# Brake.net
KiCad netlist of a schematic drawn in Altium Designer
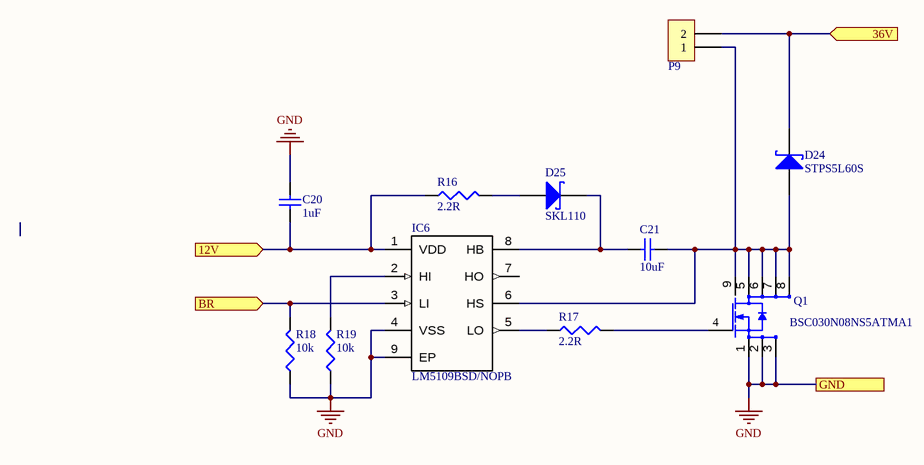
[diagram p0: Brake.SchDoc]

(export (version "E")
  (design (tool "Eeschema 10.0.6"))
  (components
    (comp (ref "C20")
      (value "1uF")
      (footprint "C1608-0603")
      (description "Керамическийконденсатор")
      (libsource (lib "db") (part "Cap"))
    )
    (comp (ref "C21")
      (value "10uF")
      (footprint "C1608-0603")
      (description "Керамическийконденсатор")
      (libsource (lib "db") (part "Cap"))
    )
    (comp (ref "D24")
      (value "STPS5L60S")
      (footprint "SMCJ")
      (description "Диод Шоттки 60В 5А [SMC]")
      (libsource (lib "db") (part "STPS5L60S"))
    )
    (comp (ref "D25")
      (value "SKL110")
      (footprint "SODFL370X140-2N")
      (description "Диод Шоттки 100В 1А")
      (libsource (lib "db") (part "SKL110"))
    )
    (comp (ref "IC6")
      (value "LM5109BSD/NOPB")
      (footprint "PSON80P400X80_HS-9N")
      (description "Драйвер MOSFET")
      (libsource (lib "db") (part "LM5109BSD/NOPB"))
    )
    (comp (ref "P9")
      (value "15EDGRC-3.81-02")
      (footprint "15EDGRC-3.81-02")
      (description "Разъем штыревой на плату (папа)")
      (libsource (lib "db") (part "15EDGRC-3.81-02"))
    )
    (comp (ref "Q1")
      (value "BSC030N08NS5ATMA1")
      (footprint "PG-TDSON-8")
      (description "N - канальный MOSFET")
      (libsource (lib "db") (part "BSC030N08NS5ATMA1"))
    )
    (comp (ref "R16")
      (value "2.2R")
      (footprint "R1608-0603")
      (description "SMD резистор")
      (libsource (lib "db") (part "resistor"))
    )
    (comp (ref "R17")
      (value "2.2R")
      (footprint "R1608-0603")
      (description "SMD резистор")
      (libsource (lib "db") (part "resistor"))
    )
    (comp (ref "R18")
      (value "10k")
      (footprint "R1608-0603")
      (description "SMD резистор")
      (libsource (lib "db") (part "resistor"))
    )
    (comp (ref "R19")
      (value "10k")
      (footprint "R1608-0603")
      (description "SMD резистор")
      (libsource (lib "db") (part "resistor"))
    )
  )
  (nets
    (net (code "1") (name "/12V") (class "Default")
      (node (ref "C20") (pin "1") (pinfunction "1_1") (pintype "passive"))
      (node (ref "IC6") (pin "1") (pinfunction "VDD_1") (pintype "power_in"))
      (node (ref "R16") (pin "1") (pinfunction "1_1") (pintype "passive"))
    )
    (net (code "2") (name "/36V") (class "Default")
      (node (ref "D24") (pin "1") (pinfunction "K_1") (pintype "passive"))
      (node (ref "P9") (pin "2") (pinfunction "2_2") (pintype "passive"))
    )
    (net (code "3") (name "/BR") (class "Default")
      (node (ref "IC6") (pin "3") (pinfunction "LI_3") (pintype "input"))
      (node (ref "R18") (pin "2") (pinfunction "2_2") (pintype "passive"))
    )
    (net (code "4") (name "GND") (class "Default")
      (node (ref "C20") (pin "2") (pinfunction "2_2") (pintype "passive"))
      (node (ref "IC6") (pin "4") (pinfunction "VSS_4") (pintype "power_in"))
      (node (ref "IC6") (pin "9") (pinfunction "EP_9") (pintype "passive"))
      (node (ref "Q1") (pin "1") (pinfunction "S_1") (pintype "passive"))
      (node (ref "Q1") (pin "2") (pinfunction "S_2") (pintype "passive"))
      (node (ref "Q1") (pin "3") (pinfunction "S_3") (pintype "passive"))
      (node (ref "R18") (pin "1") (pinfunction "1_1") (pintype "passive"))
      (node (ref "R19") (pin "1") (pinfunction "1_1") (pintype "passive"))
    )
    (net (code "5") (name "Net-(D24-A)") (class "Default")
      (node (ref "C21") (pin "2") (pinfunction "2_2") (pintype "passive"))
      (node (ref "D24") (pin "2") (pinfunction "A_2") (pintype "passive"))
      (node (ref "IC6") (pin "6") (pinfunction "HS_6") (pintype "passive"))
      (node (ref "P9") (pin "1") (pinfunction "1_1") (pintype "passive"))
      (node (ref "Q1") (pin "5") (pinfunction "D_5") (pintype "passive"))
      (node (ref "Q1") (pin "6") (pinfunction "D_6") (pintype "passive"))
      (node (ref "Q1") (pin "7") (pinfunction "D_7") (pintype "passive"))
      (node (ref "Q1") (pin "8") (pinfunction "D_8") (pintype "passive"))
      (node (ref "Q1") (pin "9") (pinfunction "D_9") (pintype "passive"))
    )
    (net (code "6") (name "Net-(D25-A)") (class "Default")
      (node (ref "D25") (pin "2") (pinfunction "A_2") (pintype "passive"))
      (node (ref "R16") (pin "2") (pinfunction "2_2") (pintype "passive"))
    )
    (net (code "7") (name "Net-(D25-K)") (class "Default")
      (node (ref "C21") (pin "1") (pinfunction "1_1") (pintype "passive"))
      (node (ref "D25") (pin "1") (pinfunction "K_1") (pintype "passive"))
      (node (ref "IC6") (pin "8") (pinfunction "HB_8") (pintype "power_in"))
    )
    (net (code "8") (name "Net-(IC6-HI)") (class "Default")
      (node (ref "IC6") (pin "2") (pinfunction "HI_2") (pintype "input"))
      (node (ref "R19") (pin "2") (pinfunction "2_2") (pintype "passive"))
    )
    (net (code "9") (name "Net-(IC6-LO)") (class "Default")
      (node (ref "IC6") (pin "5") (pinfunction "LO_5") (pintype "output"))
      (node (ref "R17") (pin "1") (pinfunction "1_1") (pintype "passive"))
    )
    (net (code "10") (name "Net-(Q1-G)") (class "Default")
      (node (ref "Q1") (pin "4") (pinfunction "G_4") (pintype "passive"))
      (node (ref "R17") (pin "2") (pinfunction "2_2") (pintype "passive"))
    )
    (net (code "11") (name "unconnected-(IC6-HO-Pad7)") (class "Default")
      (node (ref "IC6") (pin "7") (pinfunction "HO_7") (pintype "output"))
    )
  )
)
